# TSOC_GROVEY_FOUR.net
KiCad netlist of a schematic drawn in EAGLE
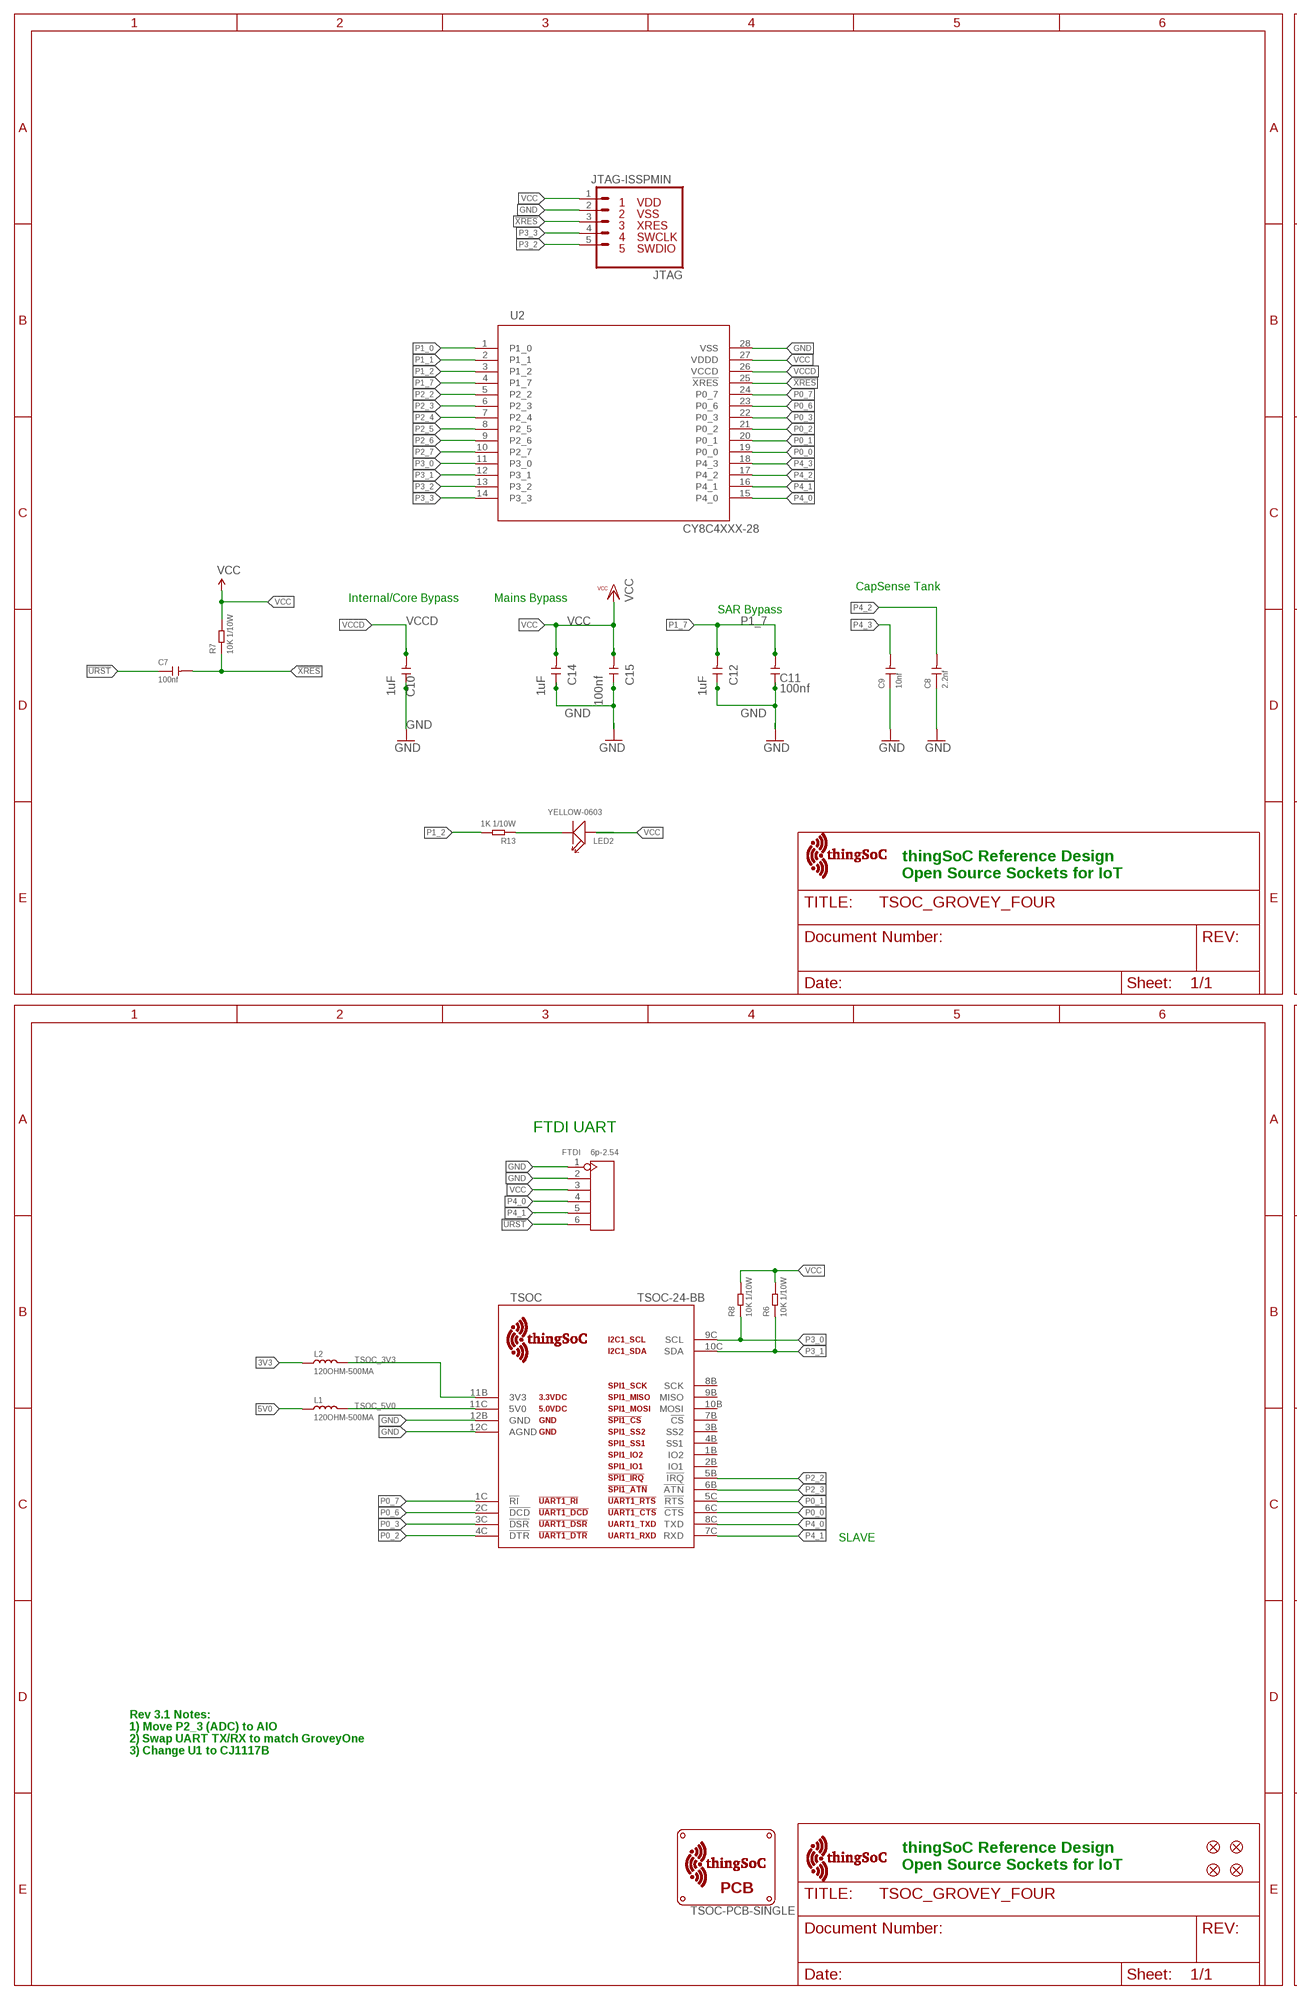
[diagram p0: schematic, sheet 1, part 1 of 2]
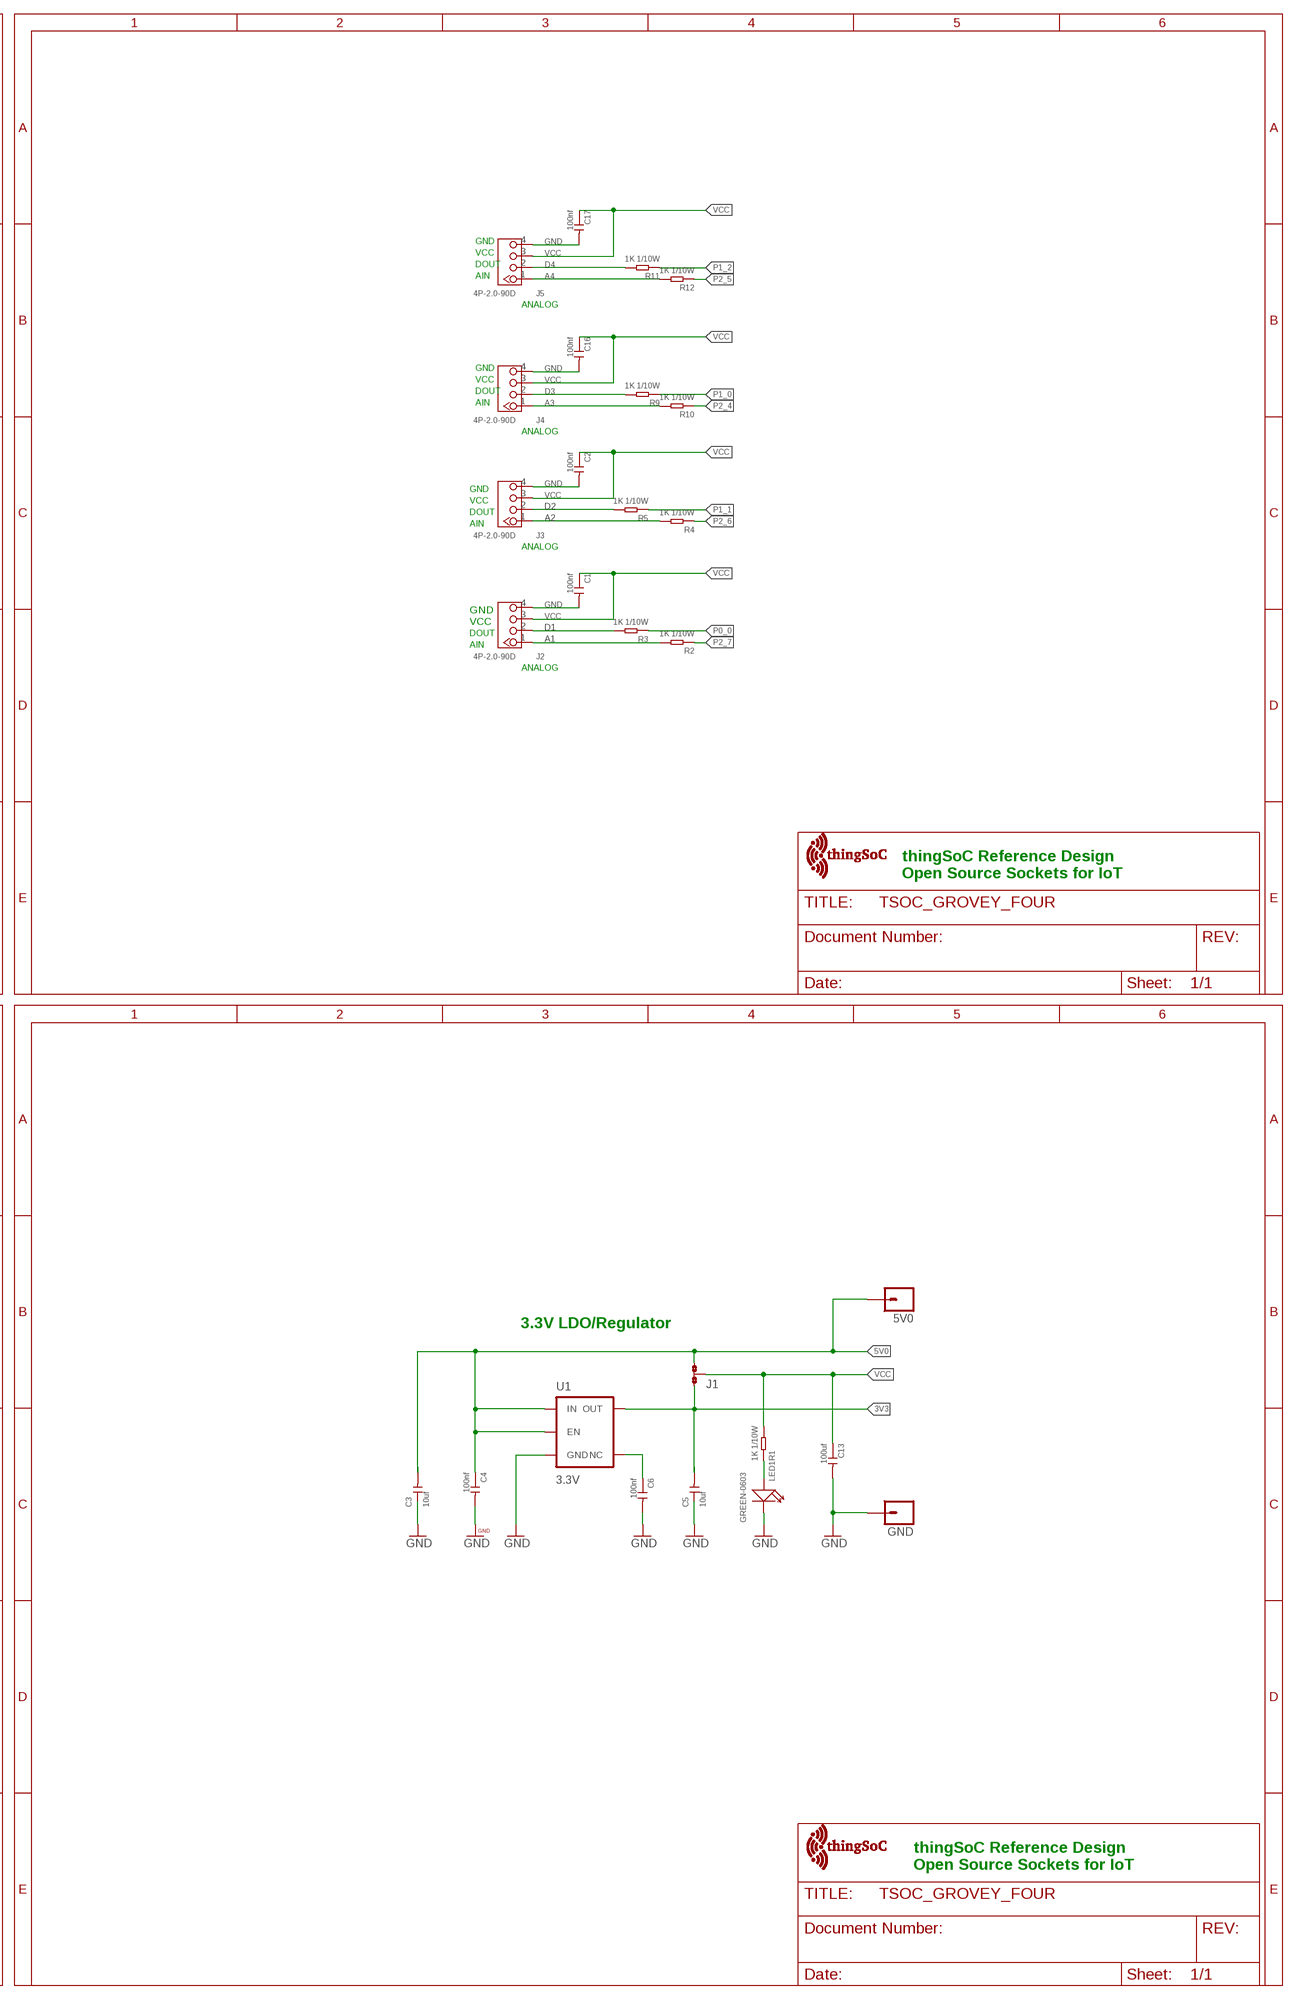
[diagram p1: schematic, sheet 1, part 2 of 2]

(export (version "E")
  (design (tool "Eeschema 10.0.6"))
  (components
    (comp (ref "$$U$1")
      (value "TSOC-PCB-SINGLE")
      (footprint "eagle-import:TSOC-BB-BRD-DIM")
      (libsource (lib "eagle-import") (part "TSOC-PCB-SINGLE"))
    )
    (comp (ref "5V0")
      (value "M01PTH")
      (footprint "eagle-import:1X01")
      (libsource (lib "eagle-import") (part "M01PTH"))
    )
    (comp (ref "C1")
      (value "100nf")
      (footprint "eagle-import:C0603")
      (fields (field (name "MPN") "CC0603KRX7R9BB104"))
      (libsource (lib "eagle-import") (part "CERAMIC-100NF-50V-10%-X7R(0603)"))
    )
    (comp (ref "C2")
      (value "100nf")
      (footprint "eagle-import:C0603")
      (fields (field (name "MPN") "CC0603KRX7R9BB104"))
      (libsource (lib "eagle-import") (part "CERAMIC-100NF-50V-10%-X7R(0603)"))
    )
    (comp (ref "C3")
      (value "10uf")
      (footprint "eagle-import:C0603")
      (fields (field (name "MPN") "CC0603KRX5R6BB106"))
      (libsource (lib "eagle-import") (part "CERAMIC-10UF-10V-10%-X5R(0603)"))
    )
    (comp (ref "C4")
      (value "100nf")
      (footprint "eagle-import:C0603")
      (fields (field (name "MPN") "CC0603KRX7R9BB104"))
      (libsource (lib "eagle-import") (part "CERAMIC-100NF-50V-10%-X7R(0603)"))
    )
    (comp (ref "C5")
      (value "10uf")
      (footprint "eagle-import:C0603")
      (fields (field (name "MPN") "CC0603KRX5R6BB106"))
      (libsource (lib "eagle-import") (part "CERAMIC-10UF-10V-10%-X5R(0603)"))
    )
    (comp (ref "C6")
      (value "100nf")
      (footprint "eagle-import:C0603")
      (fields (field (name "MPN") "CC0603KRX7R9BB104"))
      (libsource (lib "eagle-import") (part "CERAMIC-100NF-50V-10%-X7R(0603)"))
    )
    (comp (ref "C7")
      (value "100nf")
      (footprint "eagle-import:C0603")
      (fields (field (name "MPN") "CC0603KRX7R9BB104"))
      (libsource (lib "eagle-import") (part "CERAMIC-100NF-50V-10%-X7R(0603)"))
    )
    (comp (ref "C8")
      (value "2.2nf")
      (footprint "eagle-import:C0603")
      (fields (field (name "MPN") "GRM1885C1H102JA01D"))
      (libsource (lib "eagle-import") (part "CERAMIC-1NF-50V-5%-C0G(0603)"))
    )
    (comp (ref "C9")
      (value "10nf")
      (footprint "eagle-import:C0603")
      (fields (field (name "MPN") "CC0603KRX7R9BB103"))
      (libsource (lib "eagle-import") (part "CERAMIC-10NF-50V-10%-X7R(0603)"))
    )
    (comp (ref "C10")
      (value "1uF")
      (footprint "eagle-import:C0603")
      (fields (field (name "MPN") "CC0603KRX7R9BB104"))
      (libsource (lib "eagle-import") (part "CERAMIC-100NF-50V-10%-X7R(0603)"))
    )
    (comp (ref "C11")
      (value "100nf")
      (footprint "eagle-import:C0603")
      (fields (field (name "MPN") "CC0603KRX7R9BB104"))
      (libsource (lib "eagle-import") (part "CERAMIC-100NF-50V-10%-X7R(0603)"))
    )
    (comp (ref "C12")
      (value "1uF")
      (footprint "eagle-import:C0603")
      (fields (field (name "MPN") "CC0603KRX7R9BB104"))
      (libsource (lib "eagle-import") (part "CERAMIC-100NF-50V-10%-X7R(0603)"))
    )
    (comp (ref "C13")
      (value "100uf")
      (footprint "eagle-import:C1206")
      (fields (field (name "MPN") "GRM31CR60J107ME39L"))
      (libsource (lib "eagle-import") (part "CERAMIC-100UF-6.3V-20%-X5R(1206)"))
    )
    (comp (ref "C14")
      (value "1uF")
      (footprint "eagle-import:C0603")
      (fields (field (name "MPN") "CC0603KRX7R9BB104"))
      (libsource (lib "eagle-import") (part "CERAMIC-100NF-50V-10%-X7R(0603)"))
    )
    (comp (ref "C15")
      (value "100nf")
      (footprint "eagle-import:C0603")
      (fields (field (name "MPN") "CC0603KRX7R9BB104"))
      (libsource (lib "eagle-import") (part "CERAMIC-100NF-50V-10%-X7R(0603)"))
    )
    (comp (ref "C16")
      (value "100nf")
      (footprint "eagle-import:C0603")
      (fields (field (name "MPN") "CC0603KRX7R9BB104"))
      (libsource (lib "eagle-import") (part "CERAMIC-100NF-50V-10%-X7R(0603)"))
    )
    (comp (ref "C17")
      (value "100nf")
      (footprint "eagle-import:C0603")
      (fields (field (name "MPN") "CC0603KRX7R9BB104"))
      (libsource (lib "eagle-import") (part "CERAMIC-100NF-50V-10%-X7R(0603)"))
    )
    (comp (ref "FID1")
      (value "FIDUCIALUFIDUCIAL")
      (footprint "eagle-import:MICRO-FIDUCIAL")
      (libsource (lib "eagle-import") (part "FIDUCIALUFIDUCIAL"))
    )
    (comp (ref "FID2")
      (value "FIDUCIALUFIDUCIAL")
      (footprint "eagle-import:MICRO-FIDUCIAL")
      (libsource (lib "eagle-import") (part "FIDUCIALUFIDUCIAL"))
    )
    (comp (ref "FID3")
      (value "FIDUCIALUFIDUCIAL")
      (footprint "eagle-import:MICRO-FIDUCIAL")
      (libsource (lib "eagle-import") (part "FIDUCIALUFIDUCIAL"))
    )
    (comp (ref "FID4")
      (value "FIDUCIALUFIDUCIAL")
      (footprint "eagle-import:MICRO-FIDUCIAL")
      (libsource (lib "eagle-import") (part "FIDUCIALUFIDUCIAL"))
    )
    (comp (ref "FTDI")
      (value "6p-2.54")
      (footprint "eagle-import:H6-2.54")
      (fields (field (name "MPN") "P125-1106A1BS116A1"))
      (libsource (lib "eagle-import") (part "DIP-BLACK-MALE-HEADER(6P-2.54)"))
    )
    (comp (ref "GND")
      (value "M01PTH")
      (footprint "eagle-import:1X01")
      (libsource (lib "eagle-import") (part "M01PTH"))
    )
    (comp (ref "J1")
      (value "NO")
      (footprint "eagle-import:JMP-3-NO-PTH-2.54")
      (libsource (lib "eagle-import") (part "JMP-3-NO-PTH"))
    )
    (comp (ref "J2")
      (value "4P-2.0-90D")
      (footprint "eagle-import:HW4-2.0-90D")
      (libsource (lib "eagle-import") (part "GROVE-CONNECTOR-DIP-90D(4P-2.0)"))
    )
    (comp (ref "J3")
      (value "4P-2.0-90D")
      (footprint "eagle-import:HW4-2.0-90D")
      (libsource (lib "eagle-import") (part "GROVE-CONNECTOR-DIP-90D(4P-2.0)"))
    )
    (comp (ref "J4")
      (value "4P-2.0-90D")
      (footprint "eagle-import:HW4-2.0-90D")
      (libsource (lib "eagle-import") (part "GROVE-CONNECTOR-DIP-90D(4P-2.0)"))
    )
    (comp (ref "J5")
      (value "4P-2.0-90D")
      (footprint "eagle-import:HW4-2.0-90D")
      (libsource (lib "eagle-import") (part "GROVE-CONNECTOR-DIP-90D(4P-2.0)"))
    )
    (comp (ref "JTAG")
      (value "JTAG-ISSPMIN")
      (footprint "eagle-import:PSOC_JTAG_MINSILK")
      (libsource (lib "eagle-import") (part "JTAG-ISSPMIN"))
    )
    (comp (ref "L1")
      (value "120OHM-500MA")
      (footprint "eagle-import:L0603")
      (fields (field (name "MPN") "BLM18AG121SN1D"))
      (libsource (lib "eagle-import") (part "SMD-FERRITE-CHIP-120-OHM-500MA(0603)"))
    )
    (comp (ref "L2")
      (value "120OHM-500MA")
      (footprint "eagle-import:L0603")
      (fields (field (name "MPN") "BLM18AG121SN1D"))
      (libsource (lib "eagle-import") (part "SMD-FERRITE-CHIP-120-OHM-500MA(0603)"))
    )
    (comp (ref "LED1")
      (value "GREEN-0603")
      (footprint "eagle-import:LED-0603")
      (fields (field (name "MPN") "19-217-G7C-AN1P2-3T"))
      (libsource (lib "eagle-import") (part "SMD-LED-CLEAR-GREEN(0603)"))
    )
    (comp (ref "LED2")
      (value "YELLOW-0603")
      (footprint "eagle-import:LED-0603")
      (fields (field (name "MPN") "19-217-Y5C-AM1N1VY-3T"))
      (libsource (lib "eagle-import") (part "SMD-LED-CLEAR-YELLOW(0603)"))
    )
    (comp (ref "R1")
      (value "1K 1/10W")
      (footprint "eagle-import:R0603")
      (fields (field (name "MPN") "RC0603JR-071KL"))
      (libsource (lib "eagle-import") (part "SMD-RES-1K-5%-1/10W(0603)"))
    )
    (comp (ref "R2")
      (value "1K 1/10W")
      (footprint "eagle-import:R0603")
      (fields (field (name "MPN") "RC0603JR-071KL"))
      (libsource (lib "eagle-import") (part "SMD-RES-1K-5%-1/10W(0603)"))
    )
    (comp (ref "R3")
      (value "1K 1/10W")
      (footprint "eagle-import:R0603")
      (fields (field (name "MPN") "RC0603JR-071KL"))
      (libsource (lib "eagle-import") (part "SMD-RES-1K-5%-1/10W(0603)"))
    )
    (comp (ref "R4")
      (value "1K 1/10W")
      (footprint "eagle-import:R0603")
      (fields (field (name "MPN") "RC0603JR-071KL"))
      (libsource (lib "eagle-import") (part "SMD-RES-1K-5%-1/10W(0603)"))
    )
    (comp (ref "R5")
      (value "1K 1/10W")
      (footprint "eagle-import:R0603")
      (fields (field (name "MPN") "RC0603JR-071KL"))
      (libsource (lib "eagle-import") (part "SMD-RES-1K-5%-1/10W(0603)"))
    )
    (comp (ref "R6")
      (value "10K 1/10W")
      (footprint "eagle-import:R0603")
      (fields (field (name "MPN") "RC0603JR-0710KL"))
      (libsource (lib "eagle-import") (part "SMD-RES-10K-5%-1/10W(0603)"))
    )
    (comp (ref "R7")
      (value "10K 1/10W")
      (footprint "eagle-import:R0603")
      (fields (field (name "MPN") "RC0603JR-0710KL"))
      (libsource (lib "eagle-import") (part "SMD-RES-10K-5%-1/10W(0603)"))
    )
    (comp (ref "R8")
      (value "10K 1/10W")
      (footprint "eagle-import:R0603")
      (fields (field (name "MPN") "RC0603JR-0710KL"))
      (libsource (lib "eagle-import") (part "SMD-RES-10K-5%-1/10W(0603)"))
    )
    (comp (ref "R9")
      (value "1K 1/10W")
      (footprint "eagle-import:R0603")
      (fields (field (name "MPN") "RC0603JR-071KL"))
      (libsource (lib "eagle-import") (part "SMD-RES-1K-5%-1/10W(0603)"))
    )
    (comp (ref "R10")
      (value "1K 1/10W")
      (footprint "eagle-import:R0603")
      (fields (field (name "MPN") "RC0603JR-071KL"))
      (libsource (lib "eagle-import") (part "SMD-RES-1K-5%-1/10W(0603)"))
    )
    (comp (ref "R11")
      (value "1K 1/10W")
      (footprint "eagle-import:R0603")
      (fields (field (name "MPN") "RC0603JR-071KL"))
      (libsource (lib "eagle-import") (part "SMD-RES-1K-5%-1/10W(0603)"))
    )
    (comp (ref "R12")
      (value "1K 1/10W")
      (footprint "eagle-import:R0603")
      (fields (field (name "MPN") "RC0603JR-071KL"))
      (libsource (lib "eagle-import") (part "SMD-RES-1K-5%-1/10W(0603)"))
    )
    (comp (ref "R13")
      (value "1K 1/10W")
      (footprint "eagle-import:R0603")
      (fields (field (name "MPN") "RC0603JR-071KL"))
      (libsource (lib "eagle-import") (part "SMD-RES-1K-5%-1/10W(0603)"))
    )
    (comp (ref "TSOC")
      (value "TSOC-24-BB")
      (footprint "eagle-import:TSOC-BB-S24")
      (libsource (lib "eagle-import") (part "TSOC-24-BB"))
    )
    (comp (ref "U$1")
      (value "TSOC-LOGO-SMALL")
      (footprint "eagle-import:TSOC-LOGO-SML")
      (libsource (lib "eagle-import") (part "TSOC-LOGO-SMALL"))
    )
    (comp (ref "U$4")
      (value "TSOC-LOGO")
      (footprint "eagle-import:TSOC-LOGO-BLANK")
      (libsource (lib "eagle-import") (part "TSOC-LOGO"))
    )
    (comp (ref "U$101")
      (value "TSOC-LOGO-LRG")
      (footprint "eagle-import:TSOC-LOGO-LRG")
      (libsource (lib "eagle-import") (part "TSOC-LOGO-LRG"))
    )
    (comp (ref "U$102")
      (value "TSOC-LOGO-SMALL")
      (footprint "eagle-import:TSOC-LOGO-SML")
      (libsource (lib "eagle-import") (part "TSOC-LOGO-SMALL"))
    )
    (comp (ref "U1")
      (value "3.3V")
      (footprint "eagle-import:SOT23-5")
      (libsource (lib "eagle-import") (part "V_REG_AP2112K-3.3V"))
    )
    (comp (ref "U2")
      (value "CY8C4XXX-28")
      (footprint "eagle-import:SSOP28")
      (libsource (lib "eagle-import") (part "CY8C4XXX-28"))
    )
  )
  (nets
    (net (code "1") (name "/A1") (class "Default")
      (node (ref "J2") (pin "1") (pinfunction "1_1") (pintype "bidirectional"))
      (node (ref "R2") (pin "2") (pinfunction "2_2") (pintype "passive"))
    )
    (net (code "2") (name "/A2") (class "Default")
      (node (ref "J3") (pin "1") (pinfunction "1_1") (pintype "bidirectional"))
      (node (ref "R4") (pin "2") (pinfunction "2_2") (pintype "passive"))
    )
    (net (code "3") (name "/A3") (class "Default")
      (node (ref "J4") (pin "1") (pinfunction "1_1") (pintype "bidirectional"))
      (node (ref "R10") (pin "2") (pinfunction "2_2") (pintype "passive"))
    )
    (net (code "4") (name "/A4") (class "Default")
      (node (ref "J5") (pin "1") (pinfunction "1_1") (pintype "bidirectional"))
      (node (ref "R12") (pin "2") (pinfunction "2_2") (pintype "passive"))
    )
    (net (code "5") (name "/D1") (class "Default")
      (node (ref "J2") (pin "2") (pinfunction "2_2") (pintype "bidirectional"))
      (node (ref "R3") (pin "2") (pinfunction "2_2") (pintype "passive"))
    )
    (net (code "6") (name "/D2") (class "Default")
      (node (ref "J3") (pin "2") (pinfunction "2_2") (pintype "bidirectional"))
      (node (ref "R5") (pin "2") (pinfunction "2_2") (pintype "passive"))
    )
    (net (code "7") (name "/D3") (class "Default")
      (node (ref "J4") (pin "2") (pinfunction "2_2") (pintype "bidirectional"))
      (node (ref "R9") (pin "2") (pinfunction "2_2") (pintype "passive"))
    )
    (net (code "8") (name "/D4") (class "Default")
      (node (ref "J5") (pin "2") (pinfunction "2_2") (pintype "bidirectional"))
      (node (ref "R11") (pin "2") (pinfunction "2_2") (pintype "passive"))
    )
    (net (code "9") (name "/TSOC_3V3") (class "Default")
      (node (ref "L2") (pin "2") (pinfunction "2_2") (pintype "passive"))
      (node (ref "TSOC") (pin "11B") (pinfunction "3V3_11B") (pintype "bidirectional"))
    )
    (net (code "10") (name "/TSOC_5V0") (class "Default")
      (node (ref "L1") (pin "2") (pinfunction "2_2") (pintype "passive"))
      (node (ref "TSOC") (pin "11C") (pinfunction "5V0_11C") (pintype "bidirectional"))
    )
    (net (code "11") (name "/~{URST}") (class "Default")
      (node (ref "C7") (pin "1") (pinfunction "1_1") (pintype "passive"))
      (node (ref "FTDI") (pin "6") (pinfunction "6_6") (pintype "bidirectional"))
    )
    (net (code "12") (name "/~{XRES}") (class "Default")
      (node (ref "C7") (pin "2") (pinfunction "2_2") (pintype "passive"))
      (node (ref "JTAG") (pin "3") (pinfunction "3_3") (pintype "passive"))
      (node (ref "R7") (pin "1") (pinfunction "1_1") (pintype "passive"))
      (node (ref "U2") (pin "25") (pinfunction "~{XRES}_25") (pintype "bidirectional"))
    )
    (net (code "13") (name "3V3") (class "Default")
      (node (ref "C5") (pin "2") (pinfunction "2_2") (pintype "passive"))
      (node (ref "J1") (pin "1") (pinfunction "1_1") (pintype "passive"))
      (node (ref "L2") (pin "1") (pinfunction "1_1") (pintype "passive"))
      (node (ref "U1") (pin "5") (pinfunction "OUT_5") (pintype "passive"))
    )
    (net (code "14") (name "5V0") (class "Default")
      (node (ref "5V0") (pin "1") (pinfunction "1_1") (pintype "passive"))
      (node (ref "C3") (pin "2") (pinfunction "2_2") (pintype "passive"))
      (node (ref "C4") (pin "1") (pinfunction "1_1") (pintype "passive"))
      (node (ref "J1") (pin "3") (pinfunction "3_3") (pintype "passive"))
      (node (ref "L1") (pin "1") (pinfunction "1_1") (pintype "passive"))
      (node (ref "U1") (pin "1") (pinfunction "IN_1") (pintype "input"))
      (node (ref "U1") (pin "3") (pinfunction "EN_3") (pintype "input"))
    )
    (net (code "15") (name "GND") (class "Default")
      (node (ref "C1") (pin "2") (pinfunction "2_2") (pintype "passive"))
      (node (ref "C10") (pin "1") (pinfunction "1_1") (pintype "passive"))
      (node (ref "C11") (pin "1") (pinfunction "1_1") (pintype "passive"))
      (node (ref "C12") (pin "1") (pinfunction "1_1") (pintype "passive"))
      (node (ref "C13") (pin "2") (pinfunction "2_2") (pintype "passive"))
      (node (ref "C14") (pin "1") (pinfunction "1_1") (pintype "passive"))
      (node (ref "C15") (pin "1") (pinfunction "1_1") (pintype "passive"))
      (node (ref "C16") (pin "2") (pinfunction "2_2") (pintype "passive"))
      (node (ref "C17") (pin "2") (pinfunction "2_2") (pintype "passive"))
      (node (ref "C2") (pin "2") (pinfunction "2_2") (pintype "passive"))
      (node (ref "C3") (pin "1") (pinfunction "1_1") (pintype "passive"))
      (node (ref "C4") (pin "2") (pinfunction "2_2") (pintype "passive"))
      (node (ref "C5") (pin "1") (pinfunction "1_1") (pintype "passive"))
      (node (ref "C6") (pin "2") (pinfunction "2_2") (pintype "passive"))
      (node (ref "C8") (pin "1") (pinfunction "1_1") (pintype "passive"))
      (node (ref "C9") (pin "1") (pinfunction "1_1") (pintype "passive"))
      (node (ref "FTDI") (pin "1") (pinfunction "1_1") (pintype "bidirectional"))
      (node (ref "FTDI") (pin "2") (pinfunction "2_2") (pintype "bidirectional"))
      (node (ref "GND") (pin "1") (pinfunction "1_1") (pintype "passive"))
      (node (ref "J2") (pin "4") (pinfunction "4_4") (pintype "bidirectional"))
      (node (ref "J3") (pin "4") (pinfunction "4_4") (pintype "bidirectional"))
      (node (ref "J4") (pin "4") (pinfunction "4_4") (pintype "bidirectional"))
      (node (ref "J5") (pin "4") (pinfunction "4_4") (pintype "bidirectional"))
      (node (ref "JTAG") (pin "2") (pinfunction "2_2") (pintype "passive"))
      (node (ref "LED1") (pin "-") (pinfunction "-_-") (pintype "passive"))
      (node (ref "TSOC") (pin "12B") (pinfunction "GND_12B") (pintype "bidirectional"))
      (node (ref "TSOC") (pin "12C") (pinfunction "AGND_12C") (pintype "bidirectional"))
      (node (ref "U1") (pin "2") (pinfunction "GND_2") (pintype "input"))
      (node (ref "U2") (pin "28") (pinfunction "VSS_28") (pintype "bidirectional"))
    )
    (net (code "16") (name "Net-(LED1-Pad+)") (class "Default")
      (node (ref "LED1") (pin "+") (pinfunction "+_+") (pintype "passive"))
      (node (ref "R1") (pin "1") (pinfunction "1_1") (pintype "passive"))
    )
    (net (code "17") (name "Net-(LED2-Pad-)") (class "Default")
      (node (ref "LED2") (pin "-") (pinfunction "-_-") (pintype "passive"))
      (node (ref "R13") (pin "1") (pinfunction "1_1") (pintype "passive"))
    )
    (net (code "18") (name "Net-(U1-NC)") (class "Default")
      (node (ref "C6") (pin "1") (pinfunction "1_1") (pintype "passive"))
      (node (ref "U1") (pin "4") (pinfunction "NC_4") (pintype "input"))
    )
    (net (code "19") (name "P0_0") (class "Default")
      (node (ref "R3") (pin "1") (pinfunction "1_1") (pintype "passive"))
      (node (ref "TSOC") (pin "6C") (pinfunction "~{CTS}_6C") (pintype "bidirectional"))
      (node (ref "U2") (pin "19") (pinfunction "P0_0_19") (pintype "bidirectional"))
    )
    (net (code "20") (name "P0_1") (class "Default")
      (node (ref "TSOC") (pin "5C") (pinfunction "~{RTS}_5C") (pintype "bidirectional"))
      (node (ref "U2") (pin "20") (pinfunction "P0_1_20") (pintype "bidirectional"))
    )
    (net (code "21") (name "P0_2") (class "Default")
      (node (ref "TSOC") (pin "4C") (pinfunction "~{DTR}_4C") (pintype "bidirectional"))
      (node (ref "U2") (pin "21") (pinfunction "P0_2_21") (pintype "bidirectional"))
    )
    (net (code "22") (name "P0_3") (class "Default")
      (node (ref "TSOC") (pin "3C") (pinfunction "~{DSR}_3C") (pintype "bidirectional"))
      (node (ref "U2") (pin "22") (pinfunction "P0_3_22") (pintype "bidirectional"))
    )
    (net (code "23") (name "P0_6") (class "Default")
      (node (ref "TSOC") (pin "2C") (pinfunction "~{DCD}_2C") (pintype "bidirectional"))
      (node (ref "U2") (pin "23") (pinfunction "P0_6_23") (pintype "bidirectional"))
    )
    (net (code "24") (name "P0_7") (class "Default")
      (node (ref "TSOC") (pin "1C") (pinfunction "~{RI}_1C") (pintype "bidirectional"))
      (node (ref "U2") (pin "24") (pinfunction "P0_7_24") (pintype "bidirectional"))
    )
    (net (code "25") (name "P1_0") (class "Default")
      (node (ref "R9") (pin "1") (pinfunction "1_1") (pintype "passive"))
      (node (ref "U2") (pin "1") (pinfunction "P1_0_1") (pintype "bidirectional"))
    )
    (net (code "26") (name "P1_1") (class "Default")
      (node (ref "R5") (pin "1") (pinfunction "1_1") (pintype "passive"))
      (node (ref "U2") (pin "2") (pinfunction "P1_1_2") (pintype "bidirectional"))
    )
    (net (code "27") (name "P1_2") (class "Default")
      (node (ref "R11") (pin "1") (pinfunction "1_1") (pintype "passive"))
      (node (ref "R13") (pin "2") (pinfunction "2_2") (pintype "passive"))
      (node (ref "U2") (pin "3") (pinfunction "P1_2_3") (pintype "bidirectional"))
    )
    (net (code "28") (name "P1_7") (class "Default")
      (node (ref "C11") (pin "2") (pinfunction "2_2") (pintype "passive"))
      (node (ref "C12") (pin "2") (pinfunction "2_2") (pintype "passive"))
      (node (ref "U2") (pin "4") (pinfunction "P1_7_4") (pintype "bidirectional"))
    )
    (net (code "29") (name "P2_2") (class "Default")
      (node (ref "TSOC") (pin "5B") (pinfunction "~{IRQ}_5B") (pintype "bidirectional"))
      (node (ref "U2") (pin "5") (pinfunction "P2_2_5") (pintype "bidirectional"))
    )
    (net (code "30") (name "P2_3") (class "Default")
      (node (ref "TSOC") (pin "6B") (pinfunction "~{ATN}_6B") (pintype "bidirectional"))
      (node (ref "U2") (pin "6") (pinfunction "P2_3_6") (pintype "bidirectional"))
    )
    (net (code "31") (name "P2_4") (class "Default")
      (node (ref "R10") (pin "1") (pinfunction "1_1") (pintype "passive"))
      (node (ref "U2") (pin "7") (pinfunction "P2_4_7") (pintype "bidirectional"))
    )
    (net (code "32") (name "P2_5") (class "Default")
      (node (ref "R12") (pin "1") (pinfunction "1_1") (pintype "passive"))
      (node (ref "U2") (pin "8") (pinfunction "P2_5_8") (pintype "bidirectional"))
    )
    (net (code "33") (name "P2_6") (class "Default")
      (node (ref "R4") (pin "1") (pinfunction "1_1") (pintype "passive"))
      (node (ref "U2") (pin "9") (pinfunction "P2_6_9") (pintype "bidirectional"))
    )
    (net (code "34") (name "P2_7") (class "Default")
      (node (ref "R2") (pin "1") (pinfunction "1_1") (pintype "passive"))
      (node (ref "U2") (pin "10") (pinfunction "P2_7_10") (pintype "bidirectional"))
    )
    (net (code "35") (name "P3_0") (class "Default")
      (node (ref "R8") (pin "1") (pinfunction "1_1") (pintype "passive"))
      (node (ref "TSOC") (pin "9C") (pinfunction "SCL_9C") (pintype "bidirectional"))
      (node (ref "U2") (pin "11") (pinfunction "P3_0_11") (pintype "bidirectional"))
    )
    (net (code "36") (name "P3_1") (class "Default")
      (node (ref "R6") (pin "1") (pinfunction "1_1") (pintype "passive"))
      (node (ref "TSOC") (pin "10C") (pinfunction "SDA_10C") (pintype "bidirectional"))
      (node (ref "U2") (pin "12") (pinfunction "P3_1_12") (pintype "bidirectional"))
    )
    (net (code "37") (name "P3_2") (class "Default")
      (node (ref "JTAG") (pin "5") (pinfunction "5_5") (pintype "passive"))
      (node (ref "U2") (pin "13") (pinfunction "P3_2_13") (pintype "bidirectional"))
    )
    (net (code "38") (name "P3_3") (class "Default")
      (node (ref "JTAG") (pin "4") (pinfunction "4_4") (pintype "passive"))
      (node (ref "U2") (pin "14") (pinfunction "P3_3_14") (pintype "bidirectional"))
    )
    (net (code "39") (name "P4_0") (class "Default")
      (node (ref "FTDI") (pin "4") (pinfunction "4_4") (pintype "bidirectional"))
      (node (ref "TSOC") (pin "8C") (pinfunction "TXD_8C") (pintype "bidirectional"))
      (node (ref "U2") (pin "15") (pinfunction "P4_0_15") (pintype "bidirectional"))
    )
    (net (code "40") (name "P4_1") (class "Default")
      (node (ref "FTDI") (pin "5") (pinfunction "5_5") (pintype "bidirectional"))
      (node (ref "TSOC") (pin "7C") (pinfunction "RXD_7C") (pintype "bidirectional"))
      (node (ref "U2") (pin "16") (pinfunction "P4_1_16") (pintype "bidirectional"))
    )
    (net (code "41") (name "P4_2") (class "Default")
      (node (ref "C8") (pin "2") (pinfunction "2_2") (pintype "passive"))
      (node (ref "U2") (pin "17") (pinfunction "P4_2_17") (pintype "bidirectional"))
    )
    (net (code "42") (name "P4_3") (class "Default")
      (node (ref "C9") (pin "2") (pinfunction "2_2") (pintype "passive"))
      (node (ref "U2") (pin "18") (pinfunction "P4_3_18") (pintype "bidirectional"))
    )
    (net (code "43") (name "VCC") (class "Default")
      (node (ref "C1") (pin "1") (pinfunction "1_1") (pintype "passive"))
      (node (ref "C13") (pin "1") (pinfunction "1_1") (pintype "passive"))
      (node (ref "C14") (pin "2") (pinfunction "2_2") (pintype "passive"))
      (node (ref "C15") (pin "2") (pinfunction "2_2") (pintype "passive"))
      (node (ref "C16") (pin "1") (pinfunction "1_1") (pintype "passive"))
      (node (ref "C17") (pin "1") (pinfunction "1_1") (pintype "passive"))
      (node (ref "C2") (pin "1") (pinfunction "1_1") (pintype "passive"))
      (node (ref "FTDI") (pin "3") (pinfunction "3_3") (pintype "bidirectional"))
      (node (ref "J1") (pin "2") (pinfunction "2_2") (pintype "passive"))
      (node (ref "J2") (pin "3") (pinfunction "3_3") (pintype "bidirectional"))
      (node (ref "J3") (pin "3") (pinfunction "3_3") (pintype "bidirectional"))
      (node (ref "J4") (pin "3") (pinfunction "3_3") (pintype "bidirectional"))
      (node (ref "J5") (pin "3") (pinfunction "3_3") (pintype "bidirectional"))
      (node (ref "JTAG") (pin "1") (pinfunction "1_1") (pintype "passive"))
      (node (ref "LED2") (pin "+") (pinfunction "+_+") (pintype "passive"))
      (node (ref "R1") (pin "2") (pinfunction "2_2") (pintype "passive"))
      (node (ref "R6") (pin "2") (pinfunction "2_2") (pintype "passive"))
      (node (ref "R7") (pin "2") (pinfunction "2_2") (pintype "passive"))
      (node (ref "R8") (pin "2") (pinfunction "2_2") (pintype "passive"))
      (node (ref "U2") (pin "27") (pinfunction "VDDD_27") (pintype "bidirectional"))
    )
    (net (code "44") (name "VCCD") (class "Default")
      (node (ref "C10") (pin "2") (pinfunction "2_2") (pintype "passive"))
      (node (ref "U2") (pin "26") (pinfunction "VCCD_26") (pintype "bidirectional"))
    )
    (net (code "45") (name "unconnected-(TSOC-IO1-Pad2B)") (class "Default")
      (node (ref "TSOC") (pin "2B") (pinfunction "IO1_2B") (pintype "bidirectional"))
    )
    (net (code "46") (name "unconnected-(TSOC-IO2-Pad1B)") (class "Default")
      (node (ref "TSOC") (pin "1B") (pinfunction "IO2_1B") (pintype "bidirectional"))
    )
    (net (code "47") (name "unconnected-(TSOC-MISO-Pad9B)") (class "Default")
      (node (ref "TSOC") (pin "9B") (pinfunction "MISO_9B") (pintype "bidirectional"))
    )
    (net (code "48") (name "unconnected-(TSOC-MOSI-Pad10B)") (class "Default")
      (node (ref "TSOC") (pin "10B") (pinfunction "MOSI_10B") (pintype "bidirectional"))
    )
    (net (code "49") (name "unconnected-(TSOC-SCK-Pad8B)") (class "Default")
      (node (ref "TSOC") (pin "8B") (pinfunction "SCK_8B") (pintype "bidirectional"))
    )
    (net (code "50") (name "unconnected-(TSOC-SS1-Pad4B)") (class "Default")
      (node (ref "TSOC") (pin "4B") (pinfunction "SS1_4B") (pintype "bidirectional"))
    )
    (net (code "51") (name "unconnected-(TSOC-SS2-Pad3B)") (class "Default")
      (node (ref "TSOC") (pin "3B") (pinfunction "SS2_3B") (pintype "bidirectional"))
    )
    (net (code "52") (name "unconnected-(TSOC-~{CS}-Pad7B)") (class "Default")
      (node (ref "TSOC") (pin "7B") (pinfunction "~{CS}_7B") (pintype "bidirectional"))
    )
  )
)
